# max6_breakout.net
KiCad netlist of a schematic drawn in EAGLE
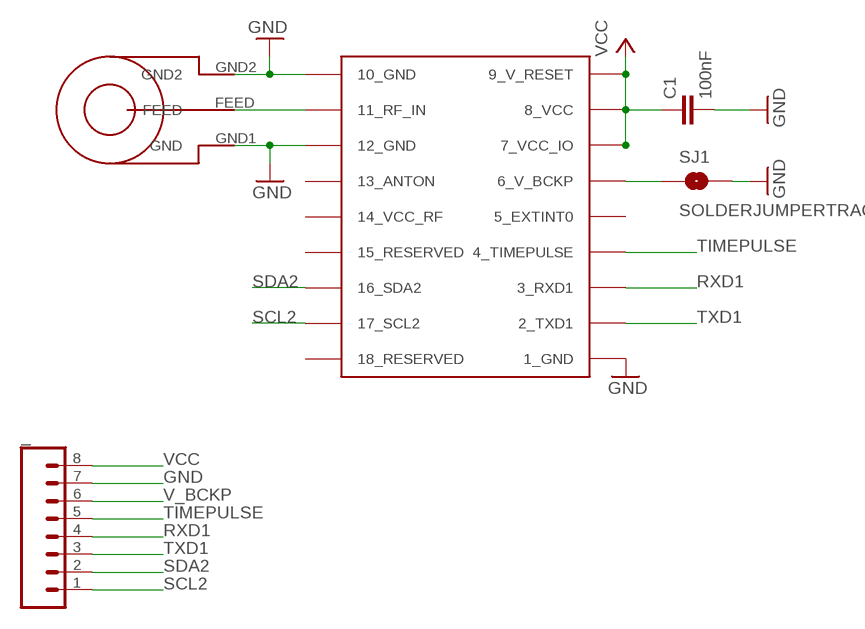
[diagram p0: schematic, sheet 1]

(export (version "E")
  (design (tool "Eeschema 10.0.6"))
  (components
    (comp (ref "C1")
      (value "100nF")
      (footprint "eagle-import:0603-CAP")
      (libsource (lib "eagle-import") (part "CAP0603-CAP"))
    )
    (comp (ref "SJ1")
      (value "SOLDERJUMPERTRACE")
      (footprint "eagle-import:SJ_2S-TRACE")
      (libsource (lib "eagle-import") (part "SOLDERJUMPERTRACE"))
    )
    (comp (ref "U$1")
      (value "UBLOX_MAX-6")
      (footprint "eagle-import:UBLOX_MAX-6")
      (libsource (lib "eagle-import") (part "UBLOX_MAX-6"))
    )
    (comp (ref "U$2")
      (value "SARANTEL-SR1202")
      (footprint "eagle-import:SARANTEL-SR1202")
      (libsource (lib "eagle-import") (part "SARANTEL-SR1202"))
    )
    (comp (ref "_")
      (value "M081X08")
      (footprint "eagle-import:1X08")
      (libsource (lib "eagle-import") (part "M081X08"))
    )
  )
  (nets
    (net (code "1") (name "/RXD1") (class "Default")
      (node (ref "U$1") (pin "3_RXD1") (pinfunction "3_RXD1_3_RXD1") (pintype "bidirectional"))
      (node (ref "_") (pin "4") (pinfunction "4_4") (pintype "passive"))
    )
    (net (code "2") (name "/SCL2") (class "Default")
      (node (ref "U$1") (pin "17_SCL2") (pinfunction "17_SCL2_17_SCL2") (pintype "bidirectional"))
      (node (ref "_") (pin "1") (pinfunction "1_1") (pintype "passive"))
    )
    (net (code "3") (name "/SDA2") (class "Default")
      (node (ref "U$1") (pin "16_SDA2") (pinfunction "16_SDA2_16_SDA2") (pintype "bidirectional"))
      (node (ref "_") (pin "2") (pinfunction "2_2") (pintype "passive"))
    )
    (net (code "4") (name "/TIMEPULSE") (class "Default")
      (node (ref "U$1") (pin "4_TIMEPULSE") (pinfunction "4_TIMEPULSE_4_TIMEPULSE") (pintype "bidirectional"))
      (node (ref "_") (pin "5") (pinfunction "5_5") (pintype "passive"))
    )
    (net (code "5") (name "/TXD1") (class "Default")
      (node (ref "U$1") (pin "2_TXD1") (pinfunction "2_TXD1_2_TXD1") (pintype "bidirectional"))
      (node (ref "_") (pin "3") (pinfunction "3_3") (pintype "passive"))
    )
    (net (code "6") (name "/V_BCKP") (class "Default")
      (node (ref "SJ1") (pin "1") (pinfunction "1_1") (pintype "passive"))
      (node (ref "U$1") (pin "6_V_BCKP") (pinfunction "6_V_BCKP_6_V_BCKP") (pintype "bidirectional"))
      (node (ref "_") (pin "6") (pinfunction "6_6") (pintype "passive"))
    )
    (net (code "7") (name "GND") (class "Default")
      (node (ref "C1") (pin "2") (pinfunction "2_2") (pintype "passive"))
      (node (ref "SJ1") (pin "2") (pinfunction "2_2") (pintype "passive"))
      (node (ref "U$1") (pin "10_GND") (pinfunction "10_GND_10_GND") (pintype "bidirectional"))
      (node (ref "U$1") (pin "12_GND") (pinfunction "12_GND_12_GND") (pintype "bidirectional"))
      (node (ref "U$1") (pin "1_GND") (pinfunction "1_GND_1_GND") (pintype "bidirectional"))
      (node (ref "U$2") (pin "GND1") (pinfunction "GND_GND1") (pintype "bidirectional"))
      (node (ref "U$2") (pin "GND2") (pinfunction "GND2_GND2") (pintype "bidirectional"))
      (node (ref "_") (pin "7") (pinfunction "7_7") (pintype "passive"))
    )
    (net (code "8") (name "Net-(U$1-Pad11_RF_IN)") (class "Default")
      (node (ref "U$1") (pin "11_RF_IN") (pinfunction "11_RF_IN_11_RF_IN") (pintype "bidirectional"))
      (node (ref "U$2") (pin "FEED") (pinfunction "FEED_FEED") (pintype "bidirectional"))
    )
    (net (code "9") (name "VCC") (class "Default")
      (node (ref "C1") (pin "1") (pinfunction "1_1") (pintype "passive"))
      (node (ref "U$1") (pin "7_VCC_IO") (pinfunction "7_VCC_IO_7_VCC_IO") (pintype "bidirectional"))
      (node (ref "U$1") (pin "8_VCC") (pinfunction "8_VCC_8_VCC") (pintype "bidirectional"))
      (node (ref "U$1") (pin "9_V_RESET") (pinfunction "9_V_RESET_9_V_RESET") (pintype "bidirectional"))
      (node (ref "_") (pin "8") (pinfunction "8_8") (pintype "passive"))
    )
    (net (code "10") (name "unconnected-(U$1-Pad5_EXTINT0)") (class "Default")
      (node (ref "U$1") (pin "5_EXTINT0") (pinfunction "5_EXTINT0_5_EXTINT0") (pintype "bidirectional"))
    )
    (net (code "11") (name "unconnected-(U$1-Pad13_ANTON)") (class "Default")
      (node (ref "U$1") (pin "13_ANTON") (pinfunction "13_ANTON_13_ANTON") (pintype "bidirectional"))
    )
    (net (code "12") (name "unconnected-(U$1-Pad14_VCC_RF)") (class "Default")
      (node (ref "U$1") (pin "14_VCC_RF") (pinfunction "14_VCC_RF_14_VCC_RF") (pintype "bidirectional"))
    )
    (net (code "13") (name "unconnected-(U$1-Pad15_RESERVED)") (class "Default")
      (node (ref "U$1") (pin "15_RESERVED") (pinfunction "15_RESERVED_15_RESERVED") (pintype "bidirectional"))
    )
    (net (code "14") (name "unconnected-(U$1-Pad18_RESERVED)") (class "Default")
      (node (ref "U$1") (pin "18_RESERVED") (pinfunction "18_RESERVED_18_RESERVED") (pintype "bidirectional"))
    )
  )
)
